# BUCK_CONVERTERS.net
KiCad netlist of a schematic drawn in Altium Designer
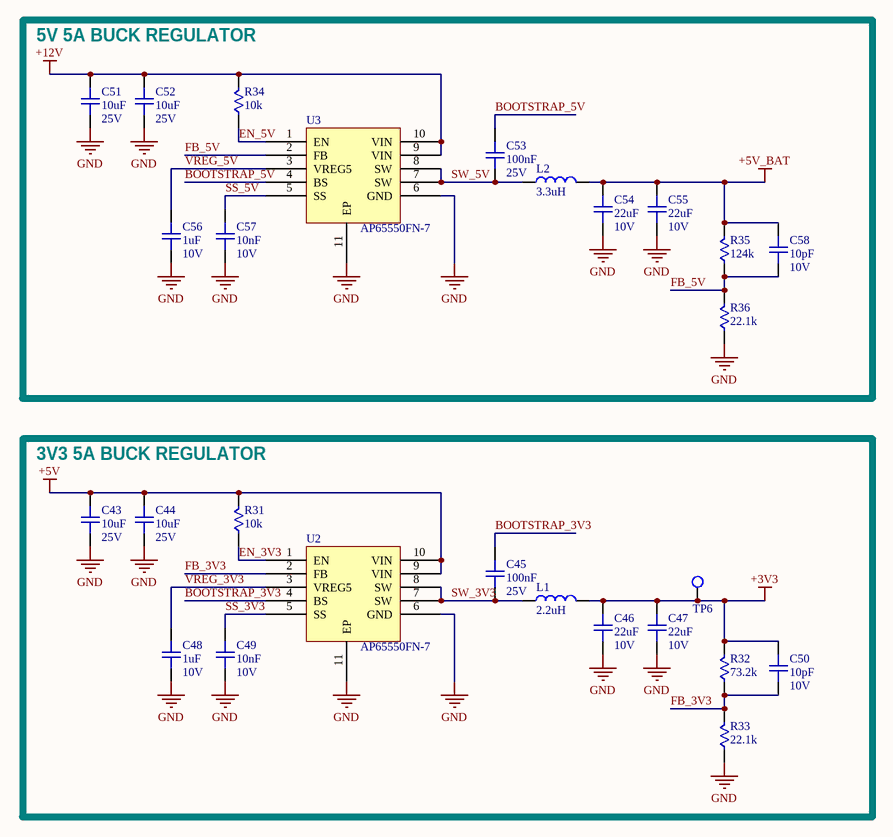
[diagram p0: BUCK_CONVERTERS.SchDoc]

(export (version "E")
  (design (tool "Eeschema 10.0.6"))
  (components
    (comp (ref "C43")
      (value "10uF")
      (footprint "R0805-3D")
      (description "CAP MLCC 10uF 25V X5R 0805")
      (fields
        (field (name "MANUFACTURER") "Taiyo Yuden")
        (field (name "MANUFACTURER PART NUMBER") "TMK212BBJ106KG-T")
        (field (name "VOLTAGE RATING (DC)") "25V")
      )
      (libsource (lib "PHANTOM_LIBRARY") (part "TMK212BBJ106KG-T"))
    )
    (comp (ref "C44")
      (value "10uF")
      (footprint "R0805-3D")
      (description "CAP MLCC 10uF 25V X5R 0805")
      (fields
        (field (name "MANUFACTURER") "Taiyo Yuden")
        (field (name "MANUFACTURER PART NUMBER") "TMK212BBJ106KG-T")
        (field (name "VOLTAGE RATING (DC)") "25V")
      )
      (libsource (lib "PHANTOM_LIBRARY") (part "TMK212BBJ106KG-T"))
    )
    (comp (ref "C45")
      (value "100nF")
      (footprint "C0402")
      (description "CAP MLCC 0.1uF 25V Y5V 0402")
      (fields
        (field (name "MANUFACTURER") "Yageo")
        (field (name "MANUFACTURER PART NUMBER") "CC0402ZRY5V8BB104")
        (field (name "VOLTAGE RATING (DC)") "25V")
      )
      (libsource (lib "PHANTOM_LIBRARY") (part "CC0402ZRY5V8BB104"))
    )
    (comp (ref "C46")
      (value "22uF")
      (footprint "R0805-3D")
      (description "CAP MLCC 22uF 10V 0805 X5R 20% SMD 0805 85C Embossed T/R")
      (fields
        (field (name "MANUFACTURER") "Murata")
        (field (name "MANUFACTURER PART NUMBER") "GRM21BR61A226ME51L")
        (field (name "VOLTAGE RATING (DC)") "10V")
      )
      (libsource (lib "PHANTOM_LIBRARY") (part "GRM21BR61A226ME51L"))
    )
    (comp (ref "C47")
      (value "22uF")
      (footprint "R0805-3D")
      (description "CAP MLCC 22uF 10V 0805 X5R 20% SMD 0805 85C Embossed T/R")
      (fields
        (field (name "MANUFACTURER") "Murata")
        (field (name "MANUFACTURER PART NUMBER") "GRM21BR61A226ME51L")
        (field (name "VOLTAGE RATING (DC)") "10V")
      )
      (libsource (lib "PHANTOM_LIBRARY") (part "GRM21BR61A226ME51L"))
    )
    (comp (ref "C48")
      (value "1uF")
      (footprint "C0402")
      (description "CAP MLCC 1uF 10V 0402 X5R 20% SMD 0402 85C Paper T/R")
      (fields
        (field (name "MANUFACTURER") "Samsung")
        (field (name "MANUFACTURER PART NUMBER") "CL05A105MP5NNNC")
        (field (name "VOLTAGE RATING") "10V")
      )
      (libsource (lib "PHANTOM_LIBRARY") (part "CL05A105MP5NNNC"))
    )
    (comp (ref "C49")
      (value "10nF")
      (footprint "C0402")
      (description "CAP MLCC 10nF 10V 0402 5R 10% SMD 0402 85C T/R")
      (fields
        (field (name "MANUFACTURER") "Murata")
        (field (name "MANUFACTURER PART NUMBER") "GRM155R61A103KA01D")
        (field (name "VOLTAGE RATING") "10V")
      )
      (libsource (lib "PHANTOM_LIBRARY") (part "GRM155R61A103KA01D"))
    )
    (comp (ref "C50")
      (value "10pF")
      (footprint "C0402")
      (description "CAP MLCC 10pF 10V 0402 C0G, NP0 0402 (1005 Metric) 0.039\" L x 0.020\" W (1.00mm x 0.50mm)")
      (fields
        (field (name "MANUFACTURER") "Wurth Electronics")
        (field (name "MANUFACTURER PART NUMBER") "885012005007")
        (field (name "VOLTAGE RATING") "10V")
      )
      (libsource (lib "PHANTOM_LIBRARY") (part "885012005007"))
    )
    (comp (ref "C51")
      (value "10uF")
      (footprint "R0805-3D")
      (description "CAP MLCC 10uF 25V X5R 0805")
      (fields
        (field (name "MANUFACTURER") "Taiyo Yuden")
        (field (name "MANUFACTURER PART NUMBER") "TMK212BBJ106KG-T")
        (field (name "VOLTAGE RATING (DC)") "25V")
      )
      (libsource (lib "PHANTOM_LIBRARY") (part "TMK212BBJ106KG-T"))
    )
    (comp (ref "C52")
      (value "10uF")
      (footprint "R0805-3D")
      (description "CAP MLCC 10uF 25V X5R 0805")
      (fields
        (field (name "MANUFACTURER") "Taiyo Yuden")
        (field (name "MANUFACTURER PART NUMBER") "TMK212BBJ106KG-T")
        (field (name "VOLTAGE RATING (DC)") "25V")
      )
      (libsource (lib "PHANTOM_LIBRARY") (part "TMK212BBJ106KG-T"))
    )
    (comp (ref "C53")
      (value "100nF")
      (footprint "C0402")
      (description "CAP MLCC 0.1uF 25V Y5V 0402")
      (fields
        (field (name "MANUFACTURER") "Yageo")
        (field (name "MANUFACTURER PART NUMBER") "CC0402ZRY5V8BB104")
        (field (name "VOLTAGE RATING (DC)") "25V")
      )
      (libsource (lib "PHANTOM_LIBRARY") (part "CC0402ZRY5V8BB104"))
    )
    (comp (ref "C54")
      (value "22uF")
      (footprint "R0805-3D")
      (description "CAP MLCC 22uF 10V 0805 X5R 20% SMD 0805 85C Embossed T/R")
      (fields
        (field (name "MANUFACTURER") "Murata")
        (field (name "MANUFACTURER PART NUMBER") "GRM21BR61A226ME51L")
        (field (name "VOLTAGE RATING (DC)") "10V")
      )
      (libsource (lib "PHANTOM_LIBRARY") (part "GRM21BR61A226ME51L"))
    )
    (comp (ref "C55")
      (value "22uF")
      (footprint "R0805-3D")
      (description "CAP MLCC 22uF 10V 0805 X5R 20% SMD 0805 85C Embossed T/R")
      (fields
        (field (name "MANUFACTURER") "Murata")
        (field (name "MANUFACTURER PART NUMBER") "GRM21BR61A226ME51L")
        (field (name "VOLTAGE RATING (DC)") "10V")
      )
      (libsource (lib "PHANTOM_LIBRARY") (part "GRM21BR61A226ME51L"))
    )
    (comp (ref "C56")
      (value "1uF")
      (footprint "C0402")
      (description "CAP MLCC 1uF 10V 0402 X5R 20% SMD 0402 85C Paper T/R")
      (fields
        (field (name "MANUFACTURER") "Samsung")
        (field (name "MANUFACTURER PART NUMBER") "CL05A105MP5NNNC")
        (field (name "VOLTAGE RATING") "10V")
      )
      (libsource (lib "PHANTOM_LIBRARY") (part "CL05A105MP5NNNC"))
    )
    (comp (ref "C57")
      (value "10nF")
      (footprint "C0402")
      (description "CAP MLCC 10nF 10V 0402 5R 10% SMD 0402 85C T/R")
      (fields
        (field (name "MANUFACTURER") "Murata")
        (field (name "MANUFACTURER PART NUMBER") "GRM155R61A103KA01D")
        (field (name "VOLTAGE RATING") "10V")
      )
      (libsource (lib "PHANTOM_LIBRARY") (part "GRM155R61A103KA01D"))
    )
    (comp (ref "C58")
      (value "10pF")
      (footprint "C0402")
      (description "CAP MLCC 10pF 10V 0402 C0G, NP0 0402 (1005 Metric) 0.039\" L x 0.020\" W (1.00mm x 0.50mm)")
      (fields
        (field (name "MANUFACTURER") "Wurth Electronics")
        (field (name "MANUFACTURER PART NUMBER") "885012005007")
        (field (name "VOLTAGE RATING") "10V")
      )
      (libsource (lib "PHANTOM_LIBRARY") (part "885012005007"))
    )
    (comp (ref "L1")
      (value "2.2uH")
      (footprint "IND-6mm")
      (description "IND 2.2uH 6.3A 19.2mOhm 30% 100KHz Ferrite  T/R")
      (fields
        (field (name "MANUFACTURER") "Murata")
        (field (name "MANUFACTURER PART NUMBER") "1255AY-2R2N=P3")
      )
      (libsource (lib "PHANTOM_LIBRARY") (part "1255AY-2R2N=P3"))
    )
    (comp (ref "L2")
      (value "3.3uH")
      (footprint "IND-6mm")
      (description "IND 3.3µH 6.5A 25.2 mOhm Max Nonstandard")
      (fields
        (field (name "MANUFACTURER") "Murata")
        (field (name "MANUFACTURER PART NUMBER") "1264EY-3R3N=P3")
      )
      (libsource (lib "PHANTOM_LIBRARY") (part "1264EY-3R3N=P3"))
    )
    (comp (ref "R31")
      (value "10k")
      (footprint "R0402")
      (description "RES SMD 10K OHM 5% 1/16W 0402")
      (fields
        (field (name "MANUFACTURER") "Yageo")
        (field (name "MANUFACTURER PART NUMBER") "RC0402JR-0710KL")
      )
      (libsource (lib "PHANTOM_LIBRARY") (part "RC0402JR-0710KL"))
    )
    (comp (ref "R32")
      (value "73.2k")
      (footprint "R0402")
      (description "RES SMD 73.2K Ohm 0402 1% 0.063W(1/16W) ±100ppm/C Molded SMD Automotive T/R")
      (fields
        (field (name "MANUFACTURER") "Stackpole Electronics")
        (field (name "MANUFACTURER PART NUMBER") "RMCF0402FT73K2")
      )
      (libsource (lib "PHANTOM_LIBRARY") (part "RMCF0402FT73K2"))
    )
    (comp (ref "R33")
      (value "22.1k")
      (footprint "R0402")
      (description "RES SMD 22.1K 0402 Ohm 1% 1/16W ±100ppm/C Molded SMD SMD Paper T/R")
      (fields
        (field (name "MANUFACTURER") "Stackpole Electronics")
        (field (name "MANUFACTURER PART NUMBER") "RMCF0402FT22K1")
      )
      (libsource (lib "PHANTOM_LIBRARY") (part "RMCF0402FT22K1"))
    )
    (comp (ref "R34")
      (value "10k")
      (footprint "R0402")
      (description "RES SMD 10K OHM 5% 1/16W 0402")
      (fields
        (field (name "MANUFACTURER") "Yageo")
        (field (name "MANUFACTURER PART NUMBER") "RC0402JR-0710KL")
      )
      (libsource (lib "PHANTOM_LIBRARY") (part "RC0402JR-0710KL"))
    )
    (comp (ref "R35")
      (value "124k")
      (footprint "R0402")
      (description "RES SMD 124K 0402 1% 1/16W 100ppm/C Molded SMD Paper T/R")
      (fields
        (field (name "MANUFACTURER") "Stackpole Electronics")
        (field (name "MANUFACTURER PART NUMBER") "RMCF0402FT124K")
      )
      (libsource (lib "PHANTOM_LIBRARY") (part "RMCF0402FT124K"))
    )
    (comp (ref "R36")
      (value "22.1k")
      (footprint "R0402")
      (description "RES SMD 22.1K 0402 Ohm 1% 1/16W ±100ppm/C Molded SMD SMD Paper T/R")
      (fields
        (field (name "MANUFACTURER") "Stackpole Electronics")
        (field (name "MANUFACTURER PART NUMBER") "RMCF0402FT22K1")
      )
      (libsource (lib "PHANTOM_LIBRARY") (part "RMCF0402FT22K1"))
    )
    (comp (ref "TP6")
      (value "5015")
      (footprint "TP_HOOK")
      (description "TEST POINT, PCB, SMT")
      (fields (field (name "MANUFACTURER") "Keystone Electronics"))
      (libsource (lib "PHANTOM_LIBRARY") (part "5015"))
    )
    (comp (ref "U2")
      (value "AP65550FN-7")
      (footprint "DFN-10")
      (description "IC BUCK SYNC 5A, 18V VIN MAX 650kHz COT Step-Down Conv")
      (fields (field (name "MANUFACTURER") "Diodes"))
      (libsource (lib "PHANTOM_LIBRARY") (part "AP65550FN-7"))
    )
    (comp (ref "U3")
      (value "AP65550FN-7")
      (footprint "DFN-10")
      (description "IC BUCK SYNC 5A, 18V VIN MAX 650kHz COT Step-Down Conv")
      (fields (field (name "MANUFACTURER") "Diodes"))
      (libsource (lib "PHANTOM_LIBRARY") (part "AP65550FN-7"))
    )
  )
  (nets
    (net (code "1") (name "+3V3") (class "Default")
      (node (ref "C46") (pin "2") (pinfunction "2_2") (pintype "passive"))
      (node (ref "C47") (pin "2") (pinfunction "2_2") (pintype "passive"))
      (node (ref "C50") (pin "2") (pinfunction "2_2") (pintype "passive"))
      (node (ref "L1") (pin "2") (pinfunction "2_2") (pintype "passive"))
      (node (ref "R32") (pin "2") (pinfunction "2_2") (pintype "passive"))
      (node (ref "TP6") (pin "1") (pinfunction "1_1") (pintype "passive"))
    )
    (net (code "2") (name "+5V") (class "Default")
      (node (ref "C43") (pin "2") (pinfunction "2_2") (pintype "passive"))
      (node (ref "C44") (pin "2") (pinfunction "2_2") (pintype "passive"))
      (node (ref "R31") (pin "2") (pinfunction "2_2") (pintype "passive"))
      (node (ref "U2") (pin "10") (pinfunction "VIN_10") (pintype "passive"))
      (node (ref "U2") (pin "9") (pinfunction "VIN_9") (pintype "passive"))
    )
    (net (code "3") (name "+5V_BAT") (class "Default")
      (node (ref "C54") (pin "2") (pinfunction "2_2") (pintype "passive"))
      (node (ref "C55") (pin "2") (pinfunction "2_2") (pintype "passive"))
      (node (ref "C58") (pin "2") (pinfunction "2_2") (pintype "passive"))
      (node (ref "L2") (pin "2") (pinfunction "2_2") (pintype "passive"))
      (node (ref "R35") (pin "2") (pinfunction "2_2") (pintype "passive"))
    )
    (net (code "4") (name "+12V") (class "Default")
      (node (ref "C51") (pin "2") (pinfunction "2_2") (pintype "passive"))
      (node (ref "C52") (pin "2") (pinfunction "2_2") (pintype "passive"))
      (node (ref "R34") (pin "2") (pinfunction "2_2") (pintype "passive"))
      (node (ref "U3") (pin "10") (pinfunction "VIN_10") (pintype "passive"))
      (node (ref "U3") (pin "9") (pinfunction "VIN_9") (pintype "passive"))
    )
    (net (code "5") (name "/BOOTSTRAP_3V3") (class "Default")
      (node (ref "C45") (pin "2") (pinfunction "2_2") (pintype "passive"))
      (node (ref "U2") (pin "4") (pinfunction "BS_4") (pintype "passive"))
    )
    (net (code "6") (name "/BOOTSTRAP_5V") (class "Default")
      (node (ref "C53") (pin "2") (pinfunction "2_2") (pintype "passive"))
      (node (ref "U3") (pin "4") (pinfunction "BS_4") (pintype "passive"))
    )
    (net (code "7") (name "/EN_3V3") (class "Default")
      (node (ref "R31") (pin "1") (pinfunction "1_1") (pintype "passive"))
      (node (ref "U2") (pin "1") (pinfunction "EN_1") (pintype "passive"))
    )
    (net (code "8") (name "/EN_5V") (class "Default")
      (node (ref "R34") (pin "1") (pinfunction "1_1") (pintype "passive"))
      (node (ref "U3") (pin "1") (pinfunction "EN_1") (pintype "passive"))
    )
    (net (code "9") (name "/FB_3V3") (class "Default")
      (node (ref "C50") (pin "1") (pinfunction "1_1") (pintype "passive"))
      (node (ref "R32") (pin "1") (pinfunction "1_1") (pintype "passive"))
      (node (ref "R33") (pin "2") (pinfunction "2_2") (pintype "passive"))
      (node (ref "U2") (pin "2") (pinfunction "FB_2") (pintype "passive"))
    )
    (net (code "10") (name "/FB_5V") (class "Default")
      (node (ref "C58") (pin "1") (pinfunction "1_1") (pintype "passive"))
      (node (ref "R35") (pin "1") (pinfunction "1_1") (pintype "passive"))
      (node (ref "R36") (pin "2") (pinfunction "2_2") (pintype "passive"))
      (node (ref "U3") (pin "2") (pinfunction "FB_2") (pintype "passive"))
    )
    (net (code "11") (name "/SS_3V3") (class "Default")
      (node (ref "C49") (pin "2") (pinfunction "2_2") (pintype "passive"))
      (node (ref "U2") (pin "5") (pinfunction "SS_5") (pintype "passive"))
    )
    (net (code "12") (name "/SS_5V") (class "Default")
      (node (ref "C57") (pin "2") (pinfunction "2_2") (pintype "passive"))
      (node (ref "U3") (pin "5") (pinfunction "SS_5") (pintype "passive"))
    )
    (net (code "13") (name "/SW_3V3") (class "Default")
      (node (ref "C45") (pin "1") (pinfunction "1_1") (pintype "passive"))
      (node (ref "L1") (pin "1") (pinfunction "1_1") (pintype "passive"))
      (node (ref "U2") (pin "7") (pinfunction "SW_7") (pintype "passive"))
      (node (ref "U2") (pin "8") (pinfunction "SW_8") (pintype "passive"))
    )
    (net (code "14") (name "/SW_5V") (class "Default")
      (node (ref "C53") (pin "1") (pinfunction "1_1") (pintype "passive"))
      (node (ref "L2") (pin "1") (pinfunction "1_1") (pintype "passive"))
      (node (ref "U3") (pin "7") (pinfunction "SW_7") (pintype "passive"))
      (node (ref "U3") (pin "8") (pinfunction "SW_8") (pintype "passive"))
    )
    (net (code "15") (name "/VREG_3V3") (class "Default")
      (node (ref "C48") (pin "2") (pinfunction "2_2") (pintype "passive"))
      (node (ref "U2") (pin "3") (pinfunction "VREG5_3") (pintype "passive"))
    )
    (net (code "16") (name "/VREG_5V") (class "Default")
      (node (ref "C56") (pin "2") (pinfunction "2_2") (pintype "passive"))
      (node (ref "U3") (pin "3") (pinfunction "VREG5_3") (pintype "passive"))
    )
    (net (code "17") (name "GND") (class "Default")
      (node (ref "C43") (pin "1") (pinfunction "1_1") (pintype "passive"))
      (node (ref "C44") (pin "1") (pinfunction "1_1") (pintype "passive"))
      (node (ref "C46") (pin "1") (pinfunction "1_1") (pintype "passive"))
      (node (ref "C47") (pin "1") (pinfunction "1_1") (pintype "passive"))
      (node (ref "C48") (pin "1") (pinfunction "1_1") (pintype "passive"))
      (node (ref "C49") (pin "1") (pinfunction "1_1") (pintype "passive"))
      (node (ref "C51") (pin "1") (pinfunction "1_1") (pintype "passive"))
      (node (ref "C52") (pin "1") (pinfunction "1_1") (pintype "passive"))
      (node (ref "C54") (pin "1") (pinfunction "1_1") (pintype "passive"))
      (node (ref "C55") (pin "1") (pinfunction "1_1") (pintype "passive"))
      (node (ref "C56") (pin "1") (pinfunction "1_1") (pintype "passive"))
      (node (ref "C57") (pin "1") (pinfunction "1_1") (pintype "passive"))
      (node (ref "R33") (pin "1") (pinfunction "1_1") (pintype "passive"))
      (node (ref "R36") (pin "1") (pinfunction "1_1") (pintype "passive"))
      (node (ref "U2") (pin "11") (pinfunction "EP_11") (pintype "passive"))
      (node (ref "U2") (pin "6") (pinfunction "GND_6") (pintype "passive"))
      (node (ref "U3") (pin "11") (pinfunction "EP_11") (pintype "passive"))
      (node (ref "U3") (pin "6") (pinfunction "GND_6") (pintype "passive"))
    )
  )
)
